# smart_mop.net
KiCad netlist of a schematic drawn in EAGLE
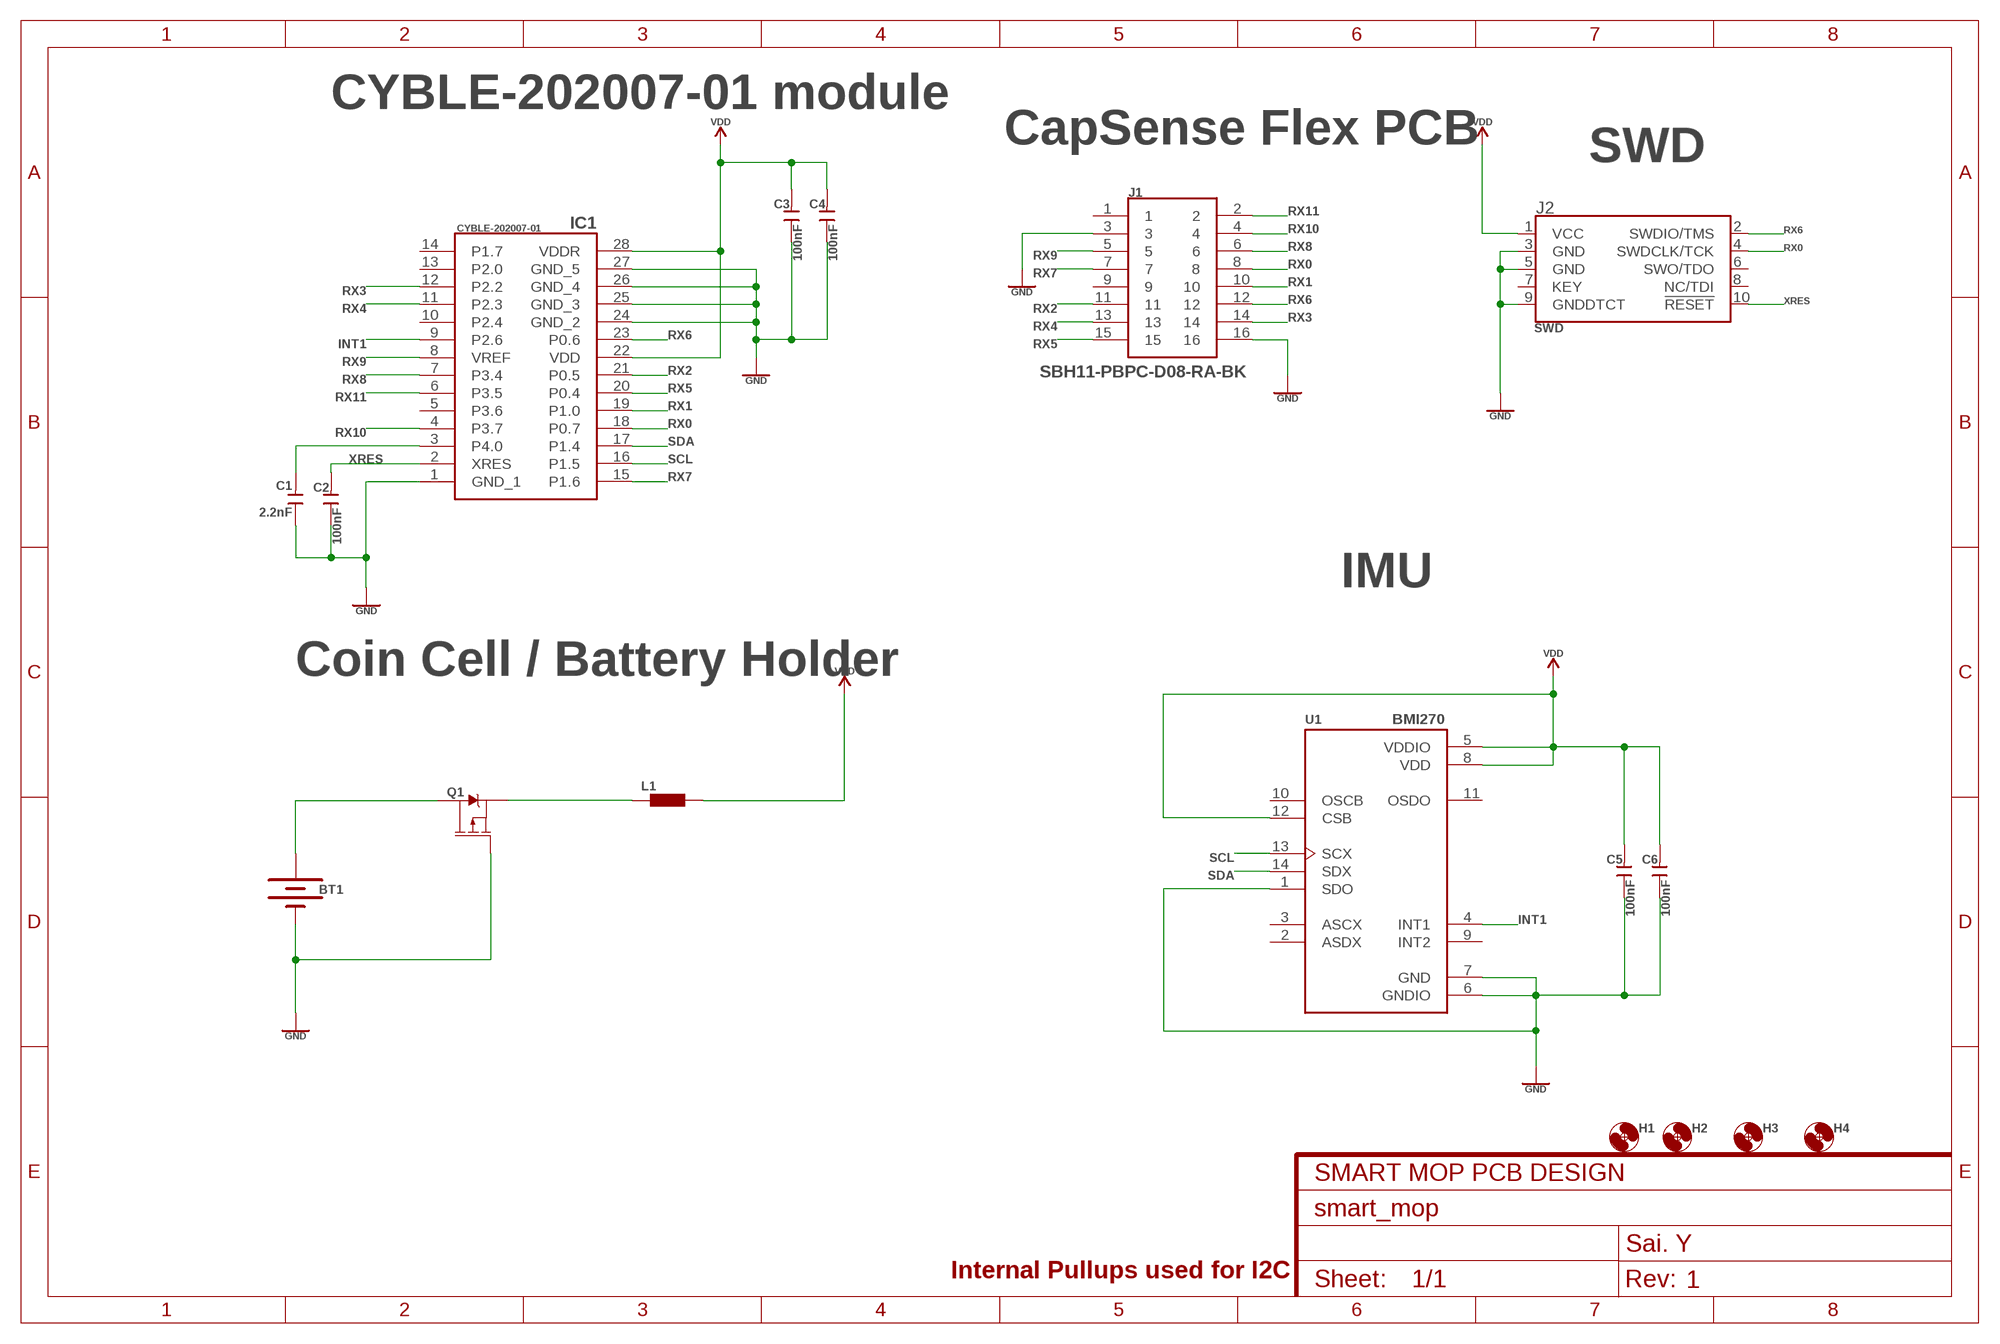
[diagram p0: schematic, sheet 1]

(export (version "E")
  (design (tool "Eeschema 10.0.6"))
  (components
    (comp (ref "BT1")
      (value "BATTERY-20MM_SMD")
      (footprint "eagle-import:BATTCON_20MM")
      (libsource (lib "eagle-import") (part "BATTERY-20MM_SMD"))
    )
    (comp (ref "C1")
      (value "2.2nF")
      (footprint "eagle-import:C0402")
      (fields (field (name "MPN") "CC0402KRX7R9BB222"))
      (libsource (lib "eagle-import") (part "CERAMIC-2.2NF-50V-10%-X7R(0402)"))
    )
    (comp (ref "C2")
      (value "100nF")
      (footprint "eagle-import:C0402")
      (fields (field (name "MPN") "CC0402KRX7R8BB104"))
      (libsource (lib "eagle-import") (part "CERAMIC-100NF-25V-10%-X7R(0402)"))
    )
    (comp (ref "C3")
      (value "100nF")
      (footprint "eagle-import:C0402")
      (fields (field (name "MPN") "CC0402KRX7R8BB104"))
      (libsource (lib "eagle-import") (part "CERAMIC-100NF-25V-10%-X7R(0402)"))
    )
    (comp (ref "C4")
      (value "100nF")
      (footprint "eagle-import:C0402")
      (fields (field (name "MPN") "CC0402KRX7R8BB104"))
      (libsource (lib "eagle-import") (part "CERAMIC-100NF-25V-10%-X7R(0402)"))
    )
    (comp (ref "C5")
      (value "100nF")
      (footprint "eagle-import:C0402")
      (fields (field (name "MPN") "CC0402KRX7R8BB104"))
      (libsource (lib "eagle-import") (part "CERAMIC-100NF-25V-10%-X7R(0402)"))
    )
    (comp (ref "C6")
      (value "100nF")
      (footprint "eagle-import:C0402")
      (fields (field (name "MPN") "CC0402KRX7R8BB104"))
      (libsource (lib "eagle-import") (part "CERAMIC-100NF-25V-10%-X7R(0402)"))
    )
    (comp (ref "H1")
      (value "MOUNT-HOLE2.8")
      (footprint "eagle-import:2,8")
      (libsource (lib "eagle-import") (part "MOUNT-HOLE2.8"))
    )
    (comp (ref "H2")
      (value "MOUNT-HOLE2.8")
      (footprint "eagle-import:2,8")
      (libsource (lib "eagle-import") (part "MOUNT-HOLE2.8"))
    )
    (comp (ref "H3")
      (value "MOUNT-HOLE2.8")
      (footprint "eagle-import:2,8")
      (libsource (lib "eagle-import") (part "MOUNT-HOLE2.8"))
    )
    (comp (ref "H4")
      (value "MOUNT-HOLE2.8")
      (footprint "eagle-import:2,8")
      (libsource (lib "eagle-import") (part "MOUNT-HOLE2.8"))
    )
    (comp (ref "IC1")
      (value "CYBLE-202007-01")
      (footprint "eagle-import:CYBLE20200701")
      (fields (field (name "MOUSER_PART_NUMBER") "727-CYBLE-202007-01"))
      (libsource (lib "eagle-import") (part "CYBLE-202007-01"))
    )
    (comp (ref "J1")
      (value "SBH11-PBPC-D08-RA-BK")
      (footprint "eagle-import:SHDRRA16W64P254_2X8_2782X910X9")
      (libsource (lib "eagle-import") (part "SBH11-PBPC-D08-RA-BK"))
    )
    (comp (ref "J2")
      (value "SWD")
      (footprint "eagle-import:SAMTECH_FTSH-105-01")
      (libsource (lib "eagle-import") (part "CORTEX_DEBUG_SMD"))
    )
    (comp (ref "L1")
      (value "BLM15HB121SN1")
      (footprint "eagle-import:0402")
      (libsource (lib "eagle-import") (part "BLM15HB121SN1"))
    )
    (comp (ref "Q1")
      (value "2.5A/30V/105mΩ")
      (footprint "eagle-import:SOT23-3")
      (libsource (lib "eagle-import") (part "MOSFET_PCH-DMG2307L"))
    )
    (comp (ref "U1")
      (value "BMI270")
      (footprint "eagle-import:XDCR_BMI270")
      (fields (field (name "MF") "Bosch Sensortec"))
      (libsource (lib "eagle-import") (part "BMI270"))
    )
  )
  (nets
    (net (code "1") (name "GND") (class "Default")
      (node (ref "BT1") (pin "2") (pinfunction "-_2") (pintype "power_in"))
      (node (ref "C1") (pin "1") (pinfunction "1_1") (pintype "passive"))
      (node (ref "C2") (pin "1") (pinfunction "1_1") (pintype "passive"))
      (node (ref "C3") (pin "1") (pinfunction "1_1") (pintype "passive"))
      (node (ref "C4") (pin "1") (pinfunction "1_1") (pintype "passive"))
      (node (ref "C5") (pin "1") (pinfunction "1_1") (pintype "passive"))
      (node (ref "C6") (pin "1") (pinfunction "1_1") (pintype "passive"))
      (node (ref "IC1") (pin "1") (pinfunction "GND_1_1") (pintype "bidirectional"))
      (node (ref "IC1") (pin "24") (pinfunction "GND_2_24") (pintype "bidirectional"))
      (node (ref "IC1") (pin "25") (pinfunction "GND_3_25") (pintype "bidirectional"))
      (node (ref "IC1") (pin "26") (pinfunction "GND_4_26") (pintype "bidirectional"))
      (node (ref "IC1") (pin "27") (pinfunction "GND_5_27") (pintype "bidirectional"))
      (node (ref "J1") (pin "16") (pinfunction "16_16") (pintype "bidirectional"))
      (node (ref "J1") (pin "3") (pinfunction "3_3") (pintype "bidirectional"))
      (node (ref "J2") (pin "3") (pinfunction "GND_3") (pintype "bidirectional"))
      (node (ref "J2") (pin "5") (pinfunction "GND_5") (pintype "bidirectional"))
      (node (ref "J2") (pin "9") (pinfunction "GNDDTCT_9") (pintype "bidirectional"))
      (node (ref "Q1") (pin "1") (pinfunction "G_1") (pintype "bidirectional"))
      (node (ref "U1") (pin "1") (pinfunction "SDO_1") (pintype "bidirectional"))
      (node (ref "U1") (pin "6") (pinfunction "GNDIO_6") (pintype "power_in"))
      (node (ref "U1") (pin "7") (pinfunction "GND_7") (pintype "power_in"))
    )
    (net (code "2") (name "INT1") (class "Default")
      (node (ref "IC1") (pin "9") (pinfunction "P2.6_9") (pintype "bidirectional"))
      (node (ref "U1") (pin "4") (pinfunction "INT1_4") (pintype "bidirectional"))
    )
    (net (code "3") (name "Net-(BT1-+)") (class "Default")
      (node (ref "BT1") (pin "1") (pinfunction "+_1") (pintype "power_in"))
      (node (ref "Q1") (pin "3") (pinfunction "D_3") (pintype "bidirectional"))
    )
    (net (code "4") (name "Net-(IC1-P4.0)") (class "Default")
      (node (ref "C1") (pin "2") (pinfunction "2_2") (pintype "passive"))
      (node (ref "IC1") (pin "3") (pinfunction "P4.0_3") (pintype "bidirectional"))
    )
    (net (code "5") (name "Net-(Q1-S)") (class "Default")
      (node (ref "L1") (pin "1") (pinfunction "1_1") (pintype "passive"))
      (node (ref "Q1") (pin "2") (pinfunction "S_2") (pintype "bidirectional"))
    )
    (net (code "6") (name "RX0") (class "Default")
      (node (ref "IC1") (pin "18") (pinfunction "P0.7_18") (pintype "bidirectional"))
      (node (ref "J1") (pin "8") (pinfunction "8_8") (pintype "bidirectional"))
      (node (ref "J2") (pin "4") (pinfunction "SWDCLK/TCK_4") (pintype "bidirectional"))
    )
    (net (code "7") (name "RX1") (class "Default")
      (node (ref "IC1") (pin "19") (pinfunction "P1.0_19") (pintype "bidirectional"))
      (node (ref "J1") (pin "10") (pinfunction "10_10") (pintype "bidirectional"))
    )
    (net (code "8") (name "RX2") (class "Default")
      (node (ref "IC1") (pin "21") (pinfunction "P0.5_21") (pintype "bidirectional"))
      (node (ref "J1") (pin "11") (pinfunction "11_11") (pintype "bidirectional"))
    )
    (net (code "9") (name "RX3") (class "Default")
      (node (ref "IC1") (pin "12") (pinfunction "P2.2_12") (pintype "bidirectional"))
      (node (ref "J1") (pin "14") (pinfunction "14_14") (pintype "bidirectional"))
    )
    (net (code "10") (name "RX4") (class "Default")
      (node (ref "IC1") (pin "11") (pinfunction "P2.3_11") (pintype "bidirectional"))
      (node (ref "J1") (pin "13") (pinfunction "13_13") (pintype "bidirectional"))
    )
    (net (code "11") (name "RX5") (class "Default")
      (node (ref "IC1") (pin "20") (pinfunction "P0.4_20") (pintype "bidirectional"))
      (node (ref "J1") (pin "15") (pinfunction "15_15") (pintype "bidirectional"))
    )
    (net (code "12") (name "RX6") (class "Default")
      (node (ref "IC1") (pin "23") (pinfunction "P0.6_23") (pintype "bidirectional"))
      (node (ref "J1") (pin "12") (pinfunction "12_12") (pintype "bidirectional"))
      (node (ref "J2") (pin "2") (pinfunction "SWDIO/TMS_2") (pintype "bidirectional"))
    )
    (net (code "13") (name "RX7") (class "Default")
      (node (ref "IC1") (pin "15") (pinfunction "P1.6_15") (pintype "bidirectional"))
      (node (ref "J1") (pin "7") (pinfunction "7_7") (pintype "bidirectional"))
    )
    (net (code "14") (name "RX8") (class "Default")
      (node (ref "IC1") (pin "7") (pinfunction "P3.4_7") (pintype "bidirectional"))
      (node (ref "J1") (pin "6") (pinfunction "6_6") (pintype "bidirectional"))
    )
    (net (code "15") (name "RX9") (class "Default")
      (node (ref "IC1") (pin "8") (pinfunction "VREF_8") (pintype "bidirectional"))
      (node (ref "J1") (pin "5") (pinfunction "5_5") (pintype "bidirectional"))
    )
    (net (code "16") (name "RX10") (class "Default")
      (node (ref "IC1") (pin "4") (pinfunction "P3.7_4") (pintype "bidirectional"))
      (node (ref "J1") (pin "4") (pinfunction "4_4") (pintype "bidirectional"))
    )
    (net (code "17") (name "RX11") (class "Default")
      (node (ref "IC1") (pin "6") (pinfunction "P3.5_6") (pintype "bidirectional"))
      (node (ref "J1") (pin "2") (pinfunction "2_2") (pintype "bidirectional"))
    )
    (net (code "18") (name "SCL") (class "Default")
      (node (ref "IC1") (pin "16") (pinfunction "P1.5_16") (pintype "bidirectional"))
      (node (ref "U1") (pin "13") (pinfunction "SCX_13") (pintype "input"))
    )
    (net (code "19") (name "SDA") (class "Default")
      (node (ref "IC1") (pin "17") (pinfunction "P1.4_17") (pintype "bidirectional"))
      (node (ref "U1") (pin "14") (pinfunction "SDX_14") (pintype "bidirectional"))
    )
    (net (code "20") (name "VDD") (class "Default")
      (node (ref "C3") (pin "2") (pinfunction "2_2") (pintype "passive"))
      (node (ref "C4") (pin "2") (pinfunction "2_2") (pintype "passive"))
      (node (ref "C5") (pin "2") (pinfunction "2_2") (pintype "passive"))
      (node (ref "C6") (pin "2") (pinfunction "2_2") (pintype "passive"))
      (node (ref "IC1") (pin "22") (pinfunction "VDD_22") (pintype "bidirectional"))
      (node (ref "IC1") (pin "28") (pinfunction "VDDR_28") (pintype "bidirectional"))
      (node (ref "J2") (pin "1") (pinfunction "VCC_1") (pintype "bidirectional"))
      (node (ref "L1") (pin "2") (pinfunction "2_2") (pintype "passive"))
      (node (ref "U1") (pin "12") (pinfunction "CSB_12") (pintype "input"))
      (node (ref "U1") (pin "5") (pinfunction "VDDIO_5") (pintype "power_in"))
      (node (ref "U1") (pin "8") (pinfunction "VDD_8") (pintype "power_in"))
    )
    (net (code "21") (name "XRES") (class "Default")
      (node (ref "C2") (pin "2") (pinfunction "2_2") (pintype "passive"))
      (node (ref "IC1") (pin "2") (pinfunction "XRES_2") (pintype "bidirectional"))
      (node (ref "J2") (pin "10") (pinfunction "~{RESET}_10") (pintype "bidirectional"))
    )
    (net (code "22") (name "unconnected-(IC1-P1.7-Pad14)") (class "Default")
      (node (ref "IC1") (pin "14") (pinfunction "P1.7_14") (pintype "bidirectional"))
    )
    (net (code "23") (name "unconnected-(IC1-P2.0-Pad13)") (class "Default")
      (node (ref "IC1") (pin "13") (pinfunction "P2.0_13") (pintype "bidirectional"))
    )
    (net (code "24") (name "unconnected-(IC1-P2.4-Pad10)") (class "Default")
      (node (ref "IC1") (pin "10") (pinfunction "P2.4_10") (pintype "bidirectional"))
    )
    (net (code "25") (name "unconnected-(IC1-P3.6-Pad5)") (class "Default")
      (node (ref "IC1") (pin "5") (pinfunction "P3.6_5") (pintype "bidirectional"))
    )
    (net (code "26") (name "unconnected-(J1-Pad1)") (class "Default")
      (node (ref "J1") (pin "1") (pinfunction "1_1") (pintype "bidirectional"))
    )
    (net (code "27") (name "unconnected-(J1-Pad9)") (class "Default")
      (node (ref "J1") (pin "9") (pinfunction "9_9") (pintype "bidirectional"))
    )
    (net (code "28") (name "unconnected-(J2-KEY-Pad7)") (class "Default")
      (node (ref "J2") (pin "7") (pinfunction "KEY_7") (pintype "bidirectional"))
    )
    (net (code "29") (name "unconnected-(J2-NC{slash}TDI-Pad8)") (class "Default")
      (node (ref "J2") (pin "8") (pinfunction "NC/TDI_8") (pintype "bidirectional"))
    )
    (net (code "30") (name "unconnected-(J2-SWO{slash}TDO-Pad6)") (class "Default")
      (node (ref "J2") (pin "6") (pinfunction "SWO/TDO_6") (pintype "bidirectional"))
    )
    (net (code "31") (name "unconnected-(U1-ASCX-Pad3)") (class "Default")
      (node (ref "U1") (pin "3") (pinfunction "ASCX_3") (pintype "bidirectional"))
    )
    (net (code "32") (name "unconnected-(U1-ASDX-Pad2)") (class "Default")
      (node (ref "U1") (pin "2") (pinfunction "ASDX_2") (pintype "bidirectional"))
    )
    (net (code "33") (name "unconnected-(U1-INT2-Pad9)") (class "Default")
      (node (ref "U1") (pin "9") (pinfunction "INT2_9") (pintype "bidirectional"))
    )
    (net (code "34") (name "unconnected-(U1-OSCB-Pad10)") (class "Default")
      (node (ref "U1") (pin "10") (pinfunction "OSCB_10") (pintype "input"))
    )
    (net (code "35") (name "unconnected-(U1-OSDO-Pad11)") (class "Default")
      (node (ref "U1") (pin "11") (pinfunction "OSDO_11") (pintype "output"))
    )
  )
)
